# esp32_audio_sch.net
KiCad netlist of a schematic drawn in Altium Designer
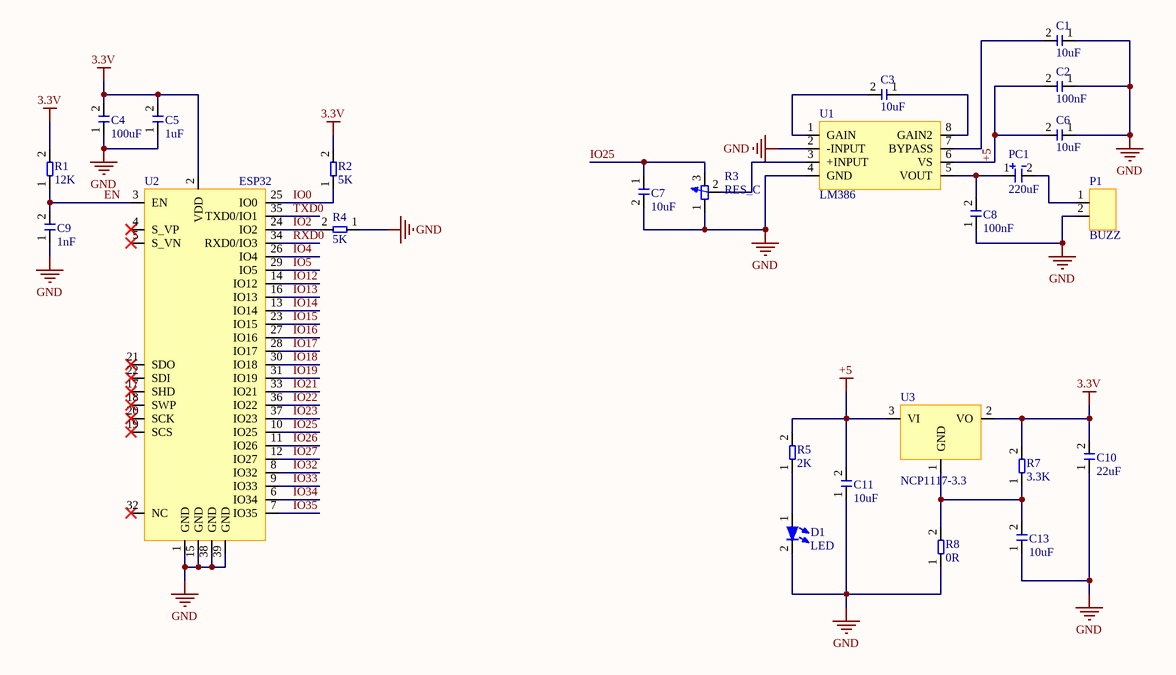
[diagram p0: esp32_audio_sch.SchDoc]

(export (version "E")
  (design (tool "Eeschema 10.0.6"))
  (components
    (comp (ref "C1")
      (value "10uF")
      (footprint "0805")
      (description "电容")
      (libsource (lib "self_schlib") (part "CAP"))
    )
    (comp (ref "C2")
      (value "100nF")
      (footprint "0805")
      (description "电容")
      (libsource (lib "self_schlib") (part "CAP"))
    )
    (comp (ref "C3")
      (value "10uF")
      (footprint "0805")
      (description "电容")
      (libsource (lib "self_schlib") (part "CAP"))
    )
    (comp (ref "C4")
      (value "100uF")
      (footprint "3216A_CAP_TAN")
      (description "电容")
      (libsource (lib "ESP_8266Schlib1") (part "CAP"))
    )
    (comp (ref "C5")
      (value "1uF")
      (footprint "3216A_CAP_TAN")
      (description "电容")
      (libsource (lib "ESP_8266Schlib1") (part "CAP"))
    )
    (comp (ref "C6")
      (value "10uF")
      (footprint "0805")
      (description "电容")
      (libsource (lib "self_schlib") (part "CAP"))
    )
    (comp (ref "C7")
      (value "10uF")
      (footprint "0805")
      (description "电容")
      (libsource (lib "self_schlib") (part "CAP"))
    )
    (comp (ref "C8")
      (value "100nF")
      (footprint "0805")
      (description "电容")
      (libsource (lib "self_schlib") (part "CAP"))
    )
    (comp (ref "C9")
      (value "1nF")
      (footprint "CAP0805")
      (description "电容")
      (libsource (lib "ESP_8266Schlib1") (part "CAP"))
    )
    (comp (ref "C10")
      (value "22uF")
      (footprint "CAP0805")
      (description "电容")
      (libsource (lib "ESP_8266Schlib1") (part "CAP"))
    )
    (comp (ref "C11")
      (value "10uF")
      (footprint "CAP0805")
      (description "电容")
      (libsource (lib "ESP_8266Schlib1") (part "CAP"))
    )
    (comp (ref "C13")
      (value "10uF")
      (footprint "CAP0805")
      (description "电容")
      (libsource (lib "ESP_8266Schlib1") (part "CAP"))
    )
    (comp (ref "D1") (value "LED") (footprint "CAP0805") (libsource (lib "ESP_8266Schlib1") (part "LED")))
    (comp (ref "P1") (value "BUZZ") (footprint "BATTERY") (libsource (lib "self_schlib") (part "BUZZ")))
    (comp (ref "PC1")
      (value "220uF")
      (footprint "DIOCAP")
      (description "极性电容")
      (libsource (lib "self_schlib") (part "PCAP"))
    )
    (comp (ref "R1")
      (value "12K")
      (footprint "CAP0805")
      (description "电阻")
      (libsource (lib "ESP_8266Schlib1") (part "RES"))
    )
    (comp (ref "R2")
      (value "5K")
      (footprint "CAP0805")
      (description "电阻")
      (libsource (lib "ESP_8266Schlib1") (part "RES"))
    )
    (comp (ref "R3") (value "RES_C") (footprint "RES_C") (libsource (lib "self_schlib") (part "RES_C")))
    (comp (ref "R4")
      (value "5K")
      (footprint "CAP0805")
      (description "电阻")
      (libsource (lib "ESP_8266Schlib1") (part "RES"))
    )
    (comp (ref "R5")
      (value "2K")
      (footprint "CAP0805")
      (description "电阻")
      (libsource (lib "ESP_8266Schlib1") (part "RES"))
    )
    (comp (ref "R7")
      (value "3.3K")
      (footprint "CAP0805")
      (description "电阻")
      (libsource (lib "ESP_8266Schlib1") (part "RES"))
    )
    (comp (ref "R8")
      (value "0R")
      (footprint "CAP0805")
      (description "电阻")
      (libsource (lib "ESP_8266Schlib1") (part "RES"))
    )
    (comp (ref "U1") (value "LM386") (footprint "DIP_8_LM386") (libsource (lib "self_schlib") (part "LM386")))
    (comp (ref "U2") (value "ESP32") (footprint "ESP32S") (libsource (lib "ESP_8266Schlib1") (part "ESP32")))
    (comp (ref "U3")
      (value "NCP1117-3.3")
      (footprint "NCP1117-33-SOT223")
      (description "NCP1117-3.3-SOT223")
      (libsource (lib "ESP_8266Schlib1") (part "NCP1117-3.3"))
    )
  )
  (nets
    (net (code "1") (name "+5") (class "Default")
      (node (ref "C11") (pin "2") (pinfunction "2_2") (pintype "passive"))
      (node (ref "C2") (pin "2") (pinfunction "2_2") (pintype "passive"))
      (node (ref "C6") (pin "2") (pinfunction "2_2") (pintype "passive"))
      (node (ref "R5") (pin "2") (pinfunction "2_2") (pintype "passive"))
      (node (ref "U1") (pin "6") (pinfunction "VS_6") (pintype "passive"))
      (node (ref "U3") (pin "3") (pinfunction "VI_3") (pintype "passive"))
    )
    (net (code "2") (name "/EN") (class "Default")
      (node (ref "C9") (pin "2") (pinfunction "2_2") (pintype "passive"))
      (node (ref "R1") (pin "1") (pinfunction "1_1") (pintype "passive"))
      (node (ref "U2") (pin "3") (pinfunction "EN_3") (pintype "passive"))
    )
    (net (code "3") (name "/IO0") (class "Default")
      (node (ref "R2") (pin "1") (pinfunction "1_1") (pintype "passive"))
      (node (ref "U2") (pin "25") (pinfunction "IO0_25") (pintype "passive"))
    )
    (net (code "4") (name "/IO2") (class "Default")
      (node (ref "R4") (pin "2") (pinfunction "2_2") (pintype "passive"))
      (node (ref "U2") (pin "24") (pinfunction "IO2_24") (pintype "passive"))
    )
    (net (code "5") (name "/IO4") (class "Default")
      (node (ref "U2") (pin "26") (pinfunction "IO4_26") (pintype "passive"))
    )
    (net (code "6") (name "/IO5") (class "Default")
      (node (ref "U2") (pin "29") (pinfunction "IO5_29") (pintype "passive"))
    )
    (net (code "7") (name "/IO12") (class "Default")
      (node (ref "U2") (pin "14") (pinfunction "IO12_14") (pintype "passive"))
    )
    (net (code "8") (name "/IO13") (class "Default")
      (node (ref "U2") (pin "16") (pinfunction "IO13_16") (pintype "passive"))
    )
    (net (code "9") (name "/IO14") (class "Default")
      (node (ref "U2") (pin "13") (pinfunction "IO14_13") (pintype "passive"))
    )
    (net (code "10") (name "/IO15") (class "Default")
      (node (ref "U2") (pin "23") (pinfunction "IO15_23") (pintype "passive"))
    )
    (net (code "11") (name "/IO16") (class "Default")
      (node (ref "U2") (pin "27") (pinfunction "IO16_27") (pintype "passive"))
    )
    (net (code "12") (name "/IO17") (class "Default")
      (node (ref "U2") (pin "28") (pinfunction "IO17_28") (pintype "passive"))
    )
    (net (code "13") (name "/IO18") (class "Default")
      (node (ref "U2") (pin "30") (pinfunction "IO18_30") (pintype "passive"))
    )
    (net (code "14") (name "/IO19") (class "Default")
      (node (ref "U2") (pin "31") (pinfunction "IO19_31") (pintype "passive"))
    )
    (net (code "15") (name "/IO21") (class "Default")
      (node (ref "U2") (pin "33") (pinfunction "IO21_33") (pintype "passive"))
    )
    (net (code "16") (name "/IO22") (class "Default")
      (node (ref "U2") (pin "36") (pinfunction "IO22_36") (pintype "passive"))
    )
    (net (code "17") (name "/IO23") (class "Default")
      (node (ref "U2") (pin "37") (pinfunction "IO23_37") (pintype "passive"))
    )
    (net (code "18") (name "/IO25") (class "Default")
      (node (ref "C7") (pin "1") (pinfunction "1_1") (pintype "passive"))
      (node (ref "R3") (pin "3") (pinfunction "3_3") (pintype "passive"))
      (node (ref "U2") (pin "10") (pinfunction "IO25_10") (pintype "passive"))
    )
    (net (code "19") (name "/IO26") (class "Default")
      (node (ref "U2") (pin "11") (pinfunction "IO26_11") (pintype "passive"))
    )
    (net (code "20") (name "/IO27") (class "Default")
      (node (ref "U2") (pin "12") (pinfunction "IO27_12") (pintype "passive"))
    )
    (net (code "21") (name "/IO32") (class "Default")
      (node (ref "U2") (pin "8") (pinfunction "IO32_8") (pintype "passive"))
    )
    (net (code "22") (name "/IO33") (class "Default")
      (node (ref "U2") (pin "9") (pinfunction "IO33_9") (pintype "passive"))
    )
    (net (code "23") (name "/IO34") (class "Default")
      (node (ref "U2") (pin "6") (pinfunction "IO34_6") (pintype "passive"))
    )
    (net (code "24") (name "/IO35") (class "Default")
      (node (ref "U2") (pin "7") (pinfunction "IO35_7") (pintype "passive"))
    )
    (net (code "25") (name "/RXD0") (class "Default")
      (node (ref "U2") (pin "34") (pinfunction "RXD0/IO3_34") (pintype "passive"))
    )
    (net (code "26") (name "/TXD0") (class "Default")
      (node (ref "U2") (pin "35") (pinfunction "TXD0/IO1_35") (pintype "passive"))
    )
    (net (code "27") (name "3.3V") (class "Default")
      (node (ref "C10") (pin "2") (pinfunction "2_2") (pintype "passive"))
      (node (ref "C4") (pin "2") (pinfunction "2_2") (pintype "passive"))
      (node (ref "C5") (pin "2") (pinfunction "2_2") (pintype "passive"))
      (node (ref "R1") (pin "2") (pinfunction "2_2") (pintype "passive"))
      (node (ref "R2") (pin "2") (pinfunction "2_2") (pintype "passive"))
      (node (ref "R7") (pin "2") (pinfunction "2_2") (pintype "passive"))
      (node (ref "U2") (pin "2") (pinfunction "VDD_2") (pintype "passive"))
      (node (ref "U3") (pin "2") (pinfunction "VO_2") (pintype "passive"))
    )
    (net (code "28") (name "GND") (class "Default")
      (node (ref "C1") (pin "1") (pinfunction "1_1") (pintype "passive"))
      (node (ref "C10") (pin "1") (pinfunction "1_1") (pintype "passive"))
      (node (ref "C11") (pin "1") (pinfunction "1_1") (pintype "passive"))
      (node (ref "C13") (pin "1") (pinfunction "1_1") (pintype "passive"))
      (node (ref "C2") (pin "1") (pinfunction "1_1") (pintype "passive"))
      (node (ref "C4") (pin "1") (pinfunction "1_1") (pintype "passive"))
      (node (ref "C5") (pin "1") (pinfunction "1_1") (pintype "passive"))
      (node (ref "C6") (pin "1") (pinfunction "1_1") (pintype "passive"))
      (node (ref "C7") (pin "2") (pinfunction "2_2") (pintype "passive"))
      (node (ref "C8") (pin "1") (pinfunction "1_1") (pintype "passive"))
      (node (ref "C9") (pin "1") (pinfunction "1_1") (pintype "passive"))
      (node (ref "D1") (pin "2") (pinfunction "2_2") (pintype "passive"))
      (node (ref "P1") (pin "2") (pinfunction "2_2") (pintype "passive"))
      (node (ref "R3") (pin "1") (pinfunction "1_1") (pintype "passive"))
      (node (ref "R4") (pin "1") (pinfunction "1_1") (pintype "passive"))
      (node (ref "R8") (pin "1") (pinfunction "1_1") (pintype "passive"))
      (node (ref "U1") (pin "2") (pinfunction "-INPUT_2") (pintype "passive"))
      (node (ref "U1") (pin "4") (pinfunction "GND_4") (pintype "passive"))
      (node (ref "U2") (pin "1") (pinfunction "GND_1") (pintype "passive"))
      (node (ref "U2") (pin "15") (pinfunction "GND_15") (pintype "passive"))
      (node (ref "U2") (pin "38") (pinfunction "GND_38") (pintype "passive"))
      (node (ref "U2") (pin "39") (pinfunction "GND_39") (pintype "passive"))
    )
    (net (code "29") (name "Net-(D1-Pad1)") (class "Default")
      (node (ref "D1") (pin "1") (pinfunction "1_1") (pintype "passive"))
      (node (ref "R5") (pin "1") (pinfunction "1_1") (pintype "passive"))
    )
    (net (code "30") (name "Net-(P1-Pad1)") (class "Default")
      (node (ref "P1") (pin "1") (pinfunction "1_1") (pintype "passive"))
      (node (ref "PC1") (pin "2") (pinfunction "2_2") (pintype "passive"))
    )
    (net (code "31") (name "Net-(U1-+INPUT)") (class "Default")
      (node (ref "R3") (pin "2") (pinfunction "2_2") (pintype "passive"))
      (node (ref "U1") (pin "3") (pinfunction "+INPUT_3") (pintype "passive"))
    )
    (net (code "32") (name "Net-(U1-BYPASS)") (class "Default")
      (node (ref "C1") (pin "2") (pinfunction "2_2") (pintype "passive"))
      (node (ref "U1") (pin "7") (pinfunction "BYPASS_7") (pintype "passive"))
    )
    (net (code "33") (name "Net-(U1-GAIN)") (class "Default")
      (node (ref "C3") (pin "2") (pinfunction "2_2") (pintype "passive"))
      (node (ref "U1") (pin "1") (pinfunction "GAIN_1") (pintype "passive"))
    )
    (net (code "34") (name "Net-(U1-GAIN2)") (class "Default")
      (node (ref "C3") (pin "1") (pinfunction "1_1") (pintype "passive"))
      (node (ref "U1") (pin "8") (pinfunction "GAIN2_8") (pintype "passive"))
    )
    (net (code "35") (name "Net-(U1-VOUT)") (class "Default")
      (node (ref "C8") (pin "2") (pinfunction "2_2") (pintype "passive"))
      (node (ref "PC1") (pin "1") (pinfunction "1_1") (pintype "passive"))
      (node (ref "U1") (pin "5") (pinfunction "VOUT_5") (pintype "passive"))
    )
    (net (code "36") (name "Net-(U3-GND)") (class "Default")
      (node (ref "C13") (pin "2") (pinfunction "2_2") (pintype "passive"))
      (node (ref "R7") (pin "1") (pinfunction "1_1") (pintype "passive"))
      (node (ref "R8") (pin "2") (pinfunction "2_2") (pintype "passive"))
      (node (ref "U3") (pin "1") (pinfunction "GND_1") (pintype "passive"))
    )
    (net (code "37") (name "unconnected-(U2-NC-Pad32)") (class "Default")
      (node (ref "U2") (pin "32") (pinfunction "NC_32") (pintype "passive+no_connect"))
    )
    (net (code "38") (name "unconnected-(U2-SCK-Pad20)") (class "Default")
      (node (ref "U2") (pin "20") (pinfunction "SCK_20") (pintype "passive+no_connect"))
    )
    (net (code "39") (name "unconnected-(U2-SCS-Pad19)") (class "Default")
      (node (ref "U2") (pin "19") (pinfunction "SCS_19") (pintype "passive+no_connect"))
    )
    (net (code "40") (name "unconnected-(U2-SDI-Pad22)") (class "Default")
      (node (ref "U2") (pin "22") (pinfunction "SDI_22") (pintype "passive+no_connect"))
    )
    (net (code "41") (name "unconnected-(U2-SDO-Pad21)") (class "Default")
      (node (ref "U2") (pin "21") (pinfunction "SDO_21") (pintype "passive+no_connect"))
    )
    (net (code "42") (name "unconnected-(U2-SHD-Pad17)") (class "Default")
      (node (ref "U2") (pin "17") (pinfunction "SHD_17") (pintype "passive+no_connect"))
    )
    (net (code "43") (name "unconnected-(U2-SWP-Pad18)") (class "Default")
      (node (ref "U2") (pin "18") (pinfunction "SWP_18") (pintype "passive+no_connect"))
    )
    (net (code "44") (name "unconnected-(U2-S_VN-Pad5)") (class "Default")
      (node (ref "U2") (pin "5") (pinfunction "S_VN_5") (pintype "passive+no_connect"))
    )
    (net (code "45") (name "unconnected-(U2-S_VP-Pad4)") (class "Default")
      (node (ref "U2") (pin "4") (pinfunction "S_VP_4") (pintype "passive+no_connect"))
    )
  )
)
